# RELAY_MODULE.net
KiCad netlist of a schematic drawn in Altium Designer
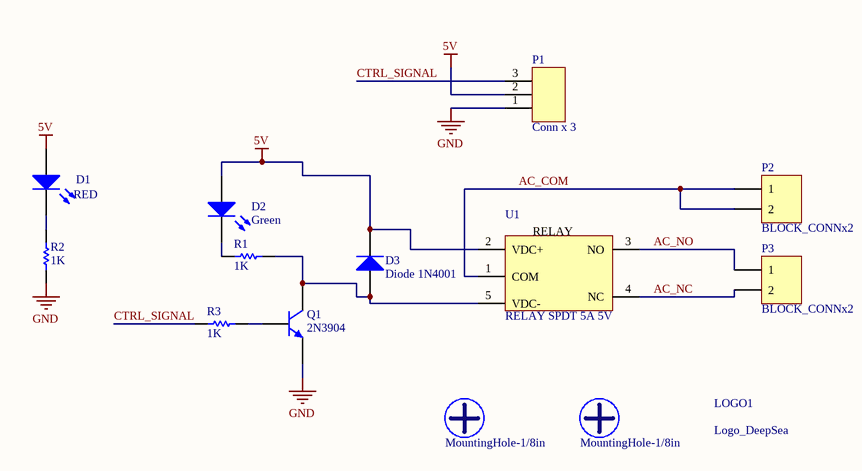
[diagram p0: RELAY_MODULE.SchDoc]

(export (version "E")
  (design (tool "Eeschema 10.0.6"))
  (components
    (comp (ref "D1")
      (value "RED")
      (footprint "R0603_L")
      (fields (field (name "COLOR") "RED"))
      (libsource (lib "General") (part "LED_SMD"))
    )
    (comp (ref "D2")
      (value "Green")
      (footprint "R0603_L")
      (fields (field (name "COLOR") "Green"))
      (libsource (lib "General") (part "LED_SMD"))
    )
    (comp (ref "D3")
      (value "Diode 1N4001")
      (footprint "DO-41")
      (description "1 Amp General Purpose Rectifier")
      (fields (field (name "PUBLISHER") "Altium Limited"))
      (libsource (lib "Miscellaneous Devices") (part "Diode 1N4001"))
    )
    (comp (ref "LOGO1")
      (value "Logo_DeepSea")
      (footprint "DeepSea_logo1")
      (libsource (lib "General") (part "Logo_DeepSea"))
    )
    (comp (ref "M1")
      (value "MountingHole-1/8in")
      (footprint "MoutingHole-1/8in")
      (libsource (lib "General") (part "MountingHole-1/8in"))
    )
    (comp (ref "M2")
      (value "MountingHole-1/8in")
      (footprint "MoutingHole-1/8in")
      (libsource (lib "General") (part "MountingHole-1/8in"))
    )
    (comp (ref "P1")
      (value "Conn x 3")
      (footprint "conn x 3")
      (description "CONN HEADER VERT 3POS .100 TIN")
      (fields
        (field (name "MANUFACTURER") "TE Connectivity")
        (field (name "MANUFACTURER PART NUMBER") "640456-3")
      )
      (libsource (lib "General") (part "Conn x 3"))
    )
    (comp (ref "P2")
      (value "BLOCK_CONNx2")
      (footprint "BLOCK_CONNX2")
      (description "TERM BLOCK 5.08MM VERT 2POS PCB")
      (fields
        (field (name "MANUFACTURER") "On Shore Technology Inc")
        (field (name "MANUFACTURER PART NUMBER") "OSTTC022162")
      )
      (libsource (lib "General") (part "BLOCK_CONNx2"))
    )
    (comp (ref "P3")
      (value "BLOCK_CONNx2")
      (footprint "BLOCK_CONNX2")
      (description "TERM BLOCK 5.08MM VERT 2POS PCB")
      (fields
        (field (name "MANUFACTURER") "On Shore Technology Inc")
        (field (name "MANUFACTURER PART NUMBER") "OSTTC022162")
      )
      (libsource (lib "General") (part "BLOCK_CONNx2"))
    )
    (comp (ref "Q1")
      (value "2N3904")
      (footprint "TO-92A")
      (description "NPN General Purpose Amplifier")
      (fields (field (name "PUBLISHER") "Altium Limited"))
      (libsource (lib "Miscellaneous Devices") (part "2N3904"))
    )
    (comp (ref "R1")
      (value "1K")
      (footprint "R0603_L")
      (fields (field (name "Comment") "R_SMD"))
      (libsource (lib "General") (part "R_SMD"))
    )
    (comp (ref "R2")
      (value "1K")
      (footprint "R0603_L")
      (fields (field (name "Comment") "R_SMD"))
      (libsource (lib "General") (part "R_SMD"))
    )
    (comp (ref "R3")
      (value "1K")
      (footprint "R0603_L")
      (fields (field (name "Comment") "R_SMD"))
      (libsource (lib "General") (part "R_SMD"))
    )
    (comp (ref "U1")
      (value "RELAY SPDT 5A 5V")
      (footprint "RELAY")
      (description "RELAY GENERAL PURPOSE SPDT 5A 5V")
      (fields
        (field (name "MANUFACTURER") "Omron Electronics Inc-EMC Div")
        (field (name "MANUFACTURER PART NUMBER") "G5LA-14 DC5")
      )
      (libsource (lib "General") (part "RELAY SPDT 5A 5V"))
    )
  )
  (nets
    (net (code "1") (name "/AC_COM") (class "Default")
      (node (ref "P2") (pin "1") (pinfunction "1_1") (pintype "passive"))
      (node (ref "P2") (pin "2") (pinfunction "2_2") (pintype "passive"))
      (node (ref "U1") (pin "1") (pinfunction "COM_1") (pintype "passive"))
    )
    (net (code "2") (name "/AC_NC") (class "Default")
      (node (ref "P3") (pin "2") (pinfunction "2_2") (pintype "passive"))
      (node (ref "U1") (pin "4") (pinfunction "NC_4") (pintype "passive"))
    )
    (net (code "3") (name "/AC_NO") (class "Default")
      (node (ref "P3") (pin "1") (pinfunction "1_1") (pintype "passive"))
      (node (ref "U1") (pin "3") (pinfunction "NO_3") (pintype "passive"))
    )
    (net (code "4") (name "/CTRL_SIGNAL") (class "Default")
      (node (ref "P1") (pin "3") (pintype "passive"))
      (node (ref "R3") (pin "2") (pinfunction "2_2") (pintype "passive"))
    )
    (net (code "5") (name "5V") (class "Default")
      (node (ref "D1") (pin "1") (pinfunction "A_1") (pintype "passive"))
      (node (ref "D2") (pin "1") (pinfunction "A_1") (pintype "passive"))
      (node (ref "D3") (pin "2") (pinfunction "K_2") (pintype "passive"))
      (node (ref "P1") (pin "2") (pintype "passive"))
      (node (ref "U1") (pin "2") (pinfunction "VDC+_2") (pintype "passive"))
    )
    (net (code "6") (name "GND") (class "Default")
      (node (ref "P1") (pin "1") (pintype "passive"))
      (node (ref "Q1") (pin "1") (pinfunction "E_1") (pintype "passive"))
      (node (ref "R2") (pin "2") (pinfunction "2_2") (pintype "passive"))
    )
    (net (code "7") (name "Net-(D1-K)") (class "Default")
      (node (ref "D1") (pin "2") (pinfunction "K_2") (pintype "passive"))
      (node (ref "R2") (pin "1") (pinfunction "1_1") (pintype "passive"))
    )
    (net (code "8") (name "Net-(D2-K)") (class "Default")
      (node (ref "D2") (pin "2") (pinfunction "K_2") (pintype "passive"))
      (node (ref "R1") (pin "2") (pinfunction "2_2") (pintype "passive"))
    )
    (net (code "9") (name "Net-(D3-A)") (class "Default")
      (node (ref "D3") (pin "1") (pinfunction "A_1") (pintype "passive"))
      (node (ref "Q1") (pin "3") (pinfunction "C_3") (pintype "passive"))
      (node (ref "R1") (pin "1") (pinfunction "1_1") (pintype "passive"))
      (node (ref "U1") (pin "5") (pinfunction "VDC-_5") (pintype "passive"))
    )
    (net (code "10") (name "Net-(Q1-B)") (class "Default")
      (node (ref "Q1") (pin "2") (pinfunction "B_2") (pintype "passive"))
      (node (ref "R3") (pin "1") (pinfunction "1_1") (pintype "passive"))
    )
  )
)
